# design.net
KiCad netlist of a schematic drawn in Altium Designer
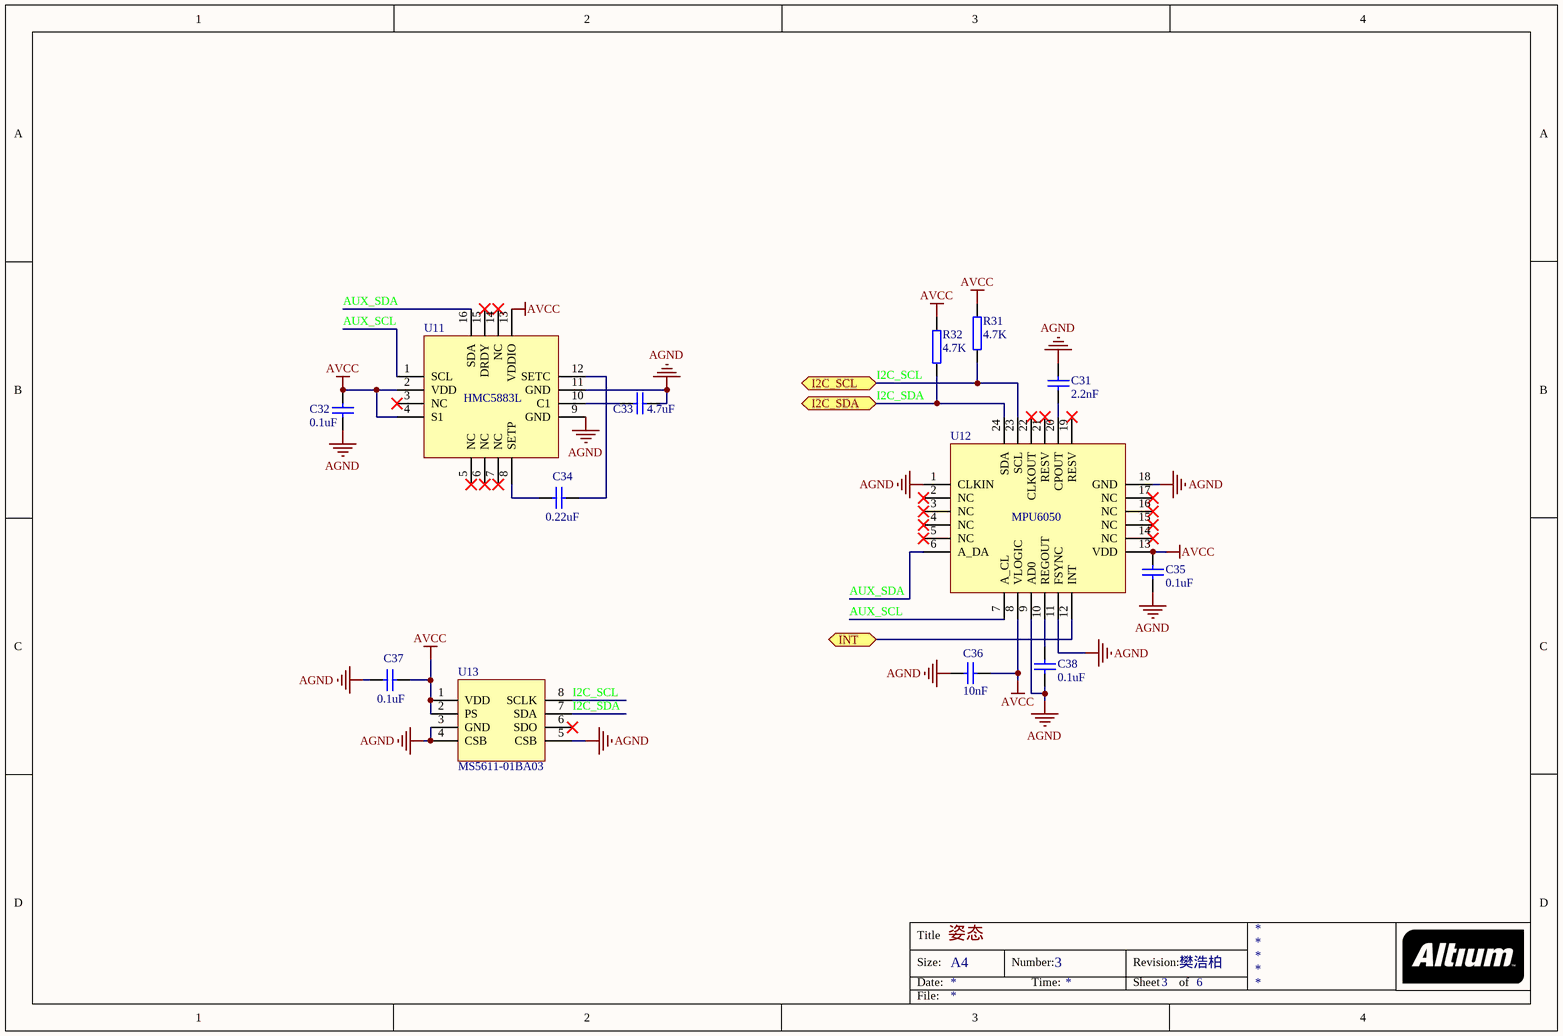
[diagram p0: 姿态.SchDoc]

(export (version "E")
  (design (tool "Eeschema 10.0.6"))
  (components
    (comp (ref "C31") (value "2.2nF") (footprint "CAP-0402") (libsource (lib "Connectors") (part "Cap")))
    (comp (ref "C32") (value "0.1uF") (footprint "CAP-0402") (libsource (lib "Connectors") (part "Cap")))
    (comp (ref "C33") (value "4.7uF") (footprint "CAP-0402") (libsource (lib "Connectors") (part "Cap")))
    (comp (ref "C34") (value "0.22uF") (footprint "CAP-0402") (libsource (lib "Connectors") (part "Cap")))
    (comp (ref "C35") (value "0.1uF") (footprint "CAP-0402") (libsource (lib "Connectors") (part "Cap")))
    (comp (ref "C36") (value "10nF") (footprint "CAP-0402") (libsource (lib "Connectors") (part "Cap")))
    (comp (ref "C37") (value "0.1uF") (footprint "CAP-0402") (libsource (lib "Connectors") (part "Cap")))
    (comp (ref "C38") (value "0.1uF") (footprint "CAP-0402") (libsource (lib "Connectors") (part "Cap")))
    (comp (ref "R31") (value "4.7K") (footprint "RES-0402") (libsource (lib "Connectors") (part "Res")))
    (comp (ref "R32") (value "4.7K") (footprint "RES-0402") (libsource (lib "Connectors") (part "Res")))
    (comp (ref "U11")
      (value "HMC5883L")
      (footprint "QFN-16-3x3MM")
      (libsource (lib "Devices") (part "HMC5883L"))
    )
    (comp (ref "U12")
      (value "MPU6050")
      (footprint "QFN-24-4x4mm")
      (libsource (lib "Devices") (part "MPU6050"))
    )
    (comp (ref "U13") (value "MS5611-01BA03") (footprint "LGA-8") (libsource (lib "Devices") (part "MS5611")))
  )
  (nets
    (net (code "1") (name "/AUX_SCL") (class "Default")
      (node (ref "U11") (pin "1") (pinfunction "SCL_1") (pintype "passive"))
      (node (ref "U12") (pin "7") (pinfunction "A_CL_7") (pintype "passive"))
    )
    (net (code "2") (name "/AUX_SDA") (class "Default")
      (node (ref "U11") (pin "16") (pinfunction "SDA_16") (pintype "passive"))
      (node (ref "U12") (pin "6") (pinfunction "A_DA_6") (pintype "passive"))
    )
    (net (code "3") (name "/I2C_SCL") (class "Default")
      (node (ref "R31") (pin "2") (pinfunction "2_2") (pintype "passive"))
      (node (ref "U12") (pin "23") (pinfunction "SCL_23") (pintype "passive"))
      (node (ref "U13") (pin "8") (pinfunction "SCLK_8") (pintype "passive"))
    )
    (net (code "4") (name "/I2C_SDA") (class "Default")
      (node (ref "R32") (pin "2") (pinfunction "2_2") (pintype "passive"))
      (node (ref "U12") (pin "24") (pinfunction "SDA_24") (pintype "passive"))
      (node (ref "U13") (pin "7") (pinfunction "SDA_7") (pintype "passive"))
    )
    (net (code "5") (name "/INT") (class "Default")
      (node (ref "U12") (pin "12") (pinfunction "INT_12") (pintype "passive"))
    )
    (net (code "6") (name "AGND") (class "Default")
      (node (ref "C31") (pin "2") (pinfunction "2_2") (pintype "passive"))
      (node (ref "C32") (pin "1") (pinfunction "1_1") (pintype "passive"))
      (node (ref "C33") (pin "1") (pinfunction "1_1") (pintype "passive"))
      (node (ref "C35") (pin "1") (pinfunction "1_1") (pintype "passive"))
      (node (ref "C36") (pin "1") (pinfunction "1_1") (pintype "passive"))
      (node (ref "C37") (pin "2") (pinfunction "2_2") (pintype "passive"))
      (node (ref "C38") (pin "1") (pinfunction "1_1") (pintype "passive"))
      (node (ref "U11") (pin "11") (pinfunction "GND_11") (pintype "passive"))
      (node (ref "U11") (pin "9") (pinfunction "GND_9") (pintype "passive"))
      (node (ref "U12") (pin "1") (pinfunction "CLKIN_1") (pintype "passive"))
      (node (ref "U12") (pin "11") (pinfunction "FSYNC_11") (pintype "passive"))
      (node (ref "U12") (pin "18") (pinfunction "GND_18") (pintype "passive"))
      (node (ref "U12") (pin "9") (pinfunction "AD0_9") (pintype "passive"))
      (node (ref "U13") (pin "3") (pinfunction "GND_3") (pintype "passive"))
      (node (ref "U13") (pin "4") (pinfunction "CSB_4") (pintype "passive"))
      (node (ref "U13") (pin "5") (pinfunction "CSB_5") (pintype "passive"))
    )
    (net (code "7") (name "AVCC") (class "Default")
      (node (ref "C32") (pin "2") (pinfunction "2_2") (pintype "passive"))
      (node (ref "C35") (pin "2") (pinfunction "2_2") (pintype "passive"))
      (node (ref "C36") (pin "2") (pinfunction "2_2") (pintype "passive"))
      (node (ref "C37") (pin "1") (pinfunction "1_1") (pintype "passive"))
      (node (ref "R31") (pin "1") (pinfunction "1_1") (pintype "passive"))
      (node (ref "R32") (pin "1") (pinfunction "1_1") (pintype "passive"))
      (node (ref "U11") (pin "13") (pinfunction "VDDIO_13") (pintype "passive"))
      (node (ref "U11") (pin "2") (pinfunction "VDD_2") (pintype "passive"))
      (node (ref "U11") (pin "4") (pinfunction "S1_4") (pintype "passive"))
      (node (ref "U12") (pin "13") (pinfunction "VDD_13") (pintype "passive"))
      (node (ref "U12") (pin "8") (pinfunction "VLOGIC_8") (pintype "passive"))
      (node (ref "U13") (pin "1") (pinfunction "VDD_1") (pintype "passive"))
      (node (ref "U13") (pin "2") (pinfunction "PS_2") (pintype "passive"))
    )
    (net (code "8") (name "Net-(U11-C1)") (class "Default")
      (node (ref "C33") (pin "2") (pinfunction "2_2") (pintype "passive"))
      (node (ref "U11") (pin "10") (pinfunction "C1_10") (pintype "passive"))
    )
    (net (code "9") (name "Net-(U11-SETC)") (class "Default")
      (node (ref "C34") (pin "1") (pinfunction "1_1") (pintype "passive"))
      (node (ref "U11") (pin "12") (pinfunction "SETC_12") (pintype "passive"))
    )
    (net (code "10") (name "Net-(U11-SETP)") (class "Default")
      (node (ref "C34") (pin "2") (pinfunction "2_2") (pintype "passive"))
      (node (ref "U11") (pin "8") (pinfunction "SETP_8") (pintype "passive"))
    )
    (net (code "11") (name "Net-(U12-CPOUT)") (class "Default")
      (node (ref "C31") (pin "1") (pinfunction "1_1") (pintype "passive"))
      (node (ref "U12") (pin "20") (pinfunction "CPOUT_20") (pintype "passive"))
    )
    (net (code "12") (name "Net-(U12-REGOUT)") (class "Default")
      (node (ref "C38") (pin "2") (pinfunction "2_2") (pintype "passive"))
      (node (ref "U12") (pin "10") (pinfunction "REGOUT_10") (pintype "passive"))
    )
    (net (code "13") (name "unconnected-(U11-DRDY-Pad15)") (class "Default")
      (node (ref "U11") (pin "15") (pinfunction "DRDY_15") (pintype "passive+no_connect"))
    )
    (net (code "14") (name "unconnected-(U11-NC-Pad3)") (class "Default")
      (node (ref "U11") (pin "3") (pinfunction "NC_3") (pintype "passive+no_connect"))
    )
    (net (code "15") (name "unconnected-(U11-NC-Pad5)") (class "Default")
      (node (ref "U11") (pin "5") (pinfunction "NC_5") (pintype "passive+no_connect"))
    )
    (net (code "16") (name "unconnected-(U11-NC-Pad6)") (class "Default")
      (node (ref "U11") (pin "6") (pinfunction "NC_6") (pintype "passive+no_connect"))
    )
    (net (code "17") (name "unconnected-(U11-NC-Pad7)") (class "Default")
      (node (ref "U11") (pin "7") (pinfunction "NC_7") (pintype "passive+no_connect"))
    )
    (net (code "18") (name "unconnected-(U11-NC-Pad14)") (class "Default")
      (node (ref "U11") (pin "14") (pinfunction "NC_14") (pintype "passive+no_connect"))
    )
    (net (code "19") (name "unconnected-(U12-CLKOUT-Pad22)") (class "Default")
      (node (ref "U12") (pin "22") (pinfunction "CLKOUT_22") (pintype "passive+no_connect"))
    )
    (net (code "20") (name "unconnected-(U12-NC-Pad2)") (class "Default")
      (node (ref "U12") (pin "2") (pinfunction "NC_2") (pintype "passive+no_connect"))
    )
    (net (code "21") (name "unconnected-(U12-NC-Pad3)") (class "Default")
      (node (ref "U12") (pin "3") (pinfunction "NC_3") (pintype "passive+no_connect"))
    )
    (net (code "22") (name "unconnected-(U12-NC-Pad4)") (class "Default")
      (node (ref "U12") (pin "4") (pinfunction "NC_4") (pintype "passive+no_connect"))
    )
    (net (code "23") (name "unconnected-(U12-NC-Pad5)") (class "Default")
      (node (ref "U12") (pin "5") (pinfunction "NC_5") (pintype "passive+no_connect"))
    )
    (net (code "24") (name "unconnected-(U12-NC-Pad14)") (class "Default")
      (node (ref "U12") (pin "14") (pinfunction "NC_14") (pintype "passive+no_connect"))
    )
    (net (code "25") (name "unconnected-(U12-NC-Pad15)") (class "Default")
      (node (ref "U12") (pin "15") (pinfunction "NC_15") (pintype "passive+no_connect"))
    )
    (net (code "26") (name "unconnected-(U12-NC-Pad16)") (class "Default")
      (node (ref "U12") (pin "16") (pinfunction "NC_16") (pintype "passive+no_connect"))
    )
    (net (code "27") (name "unconnected-(U12-NC-Pad17)") (class "Default")
      (node (ref "U12") (pin "17") (pinfunction "NC_17") (pintype "passive+no_connect"))
    )
    (net (code "28") (name "unconnected-(U12-RESV-Pad19)") (class "Default")
      (node (ref "U12") (pin "19") (pinfunction "RESV_19") (pintype "passive+no_connect"))
    )
    (net (code "29") (name "unconnected-(U12-RESV-Pad21)") (class "Default")
      (node (ref "U12") (pin "21") (pinfunction "RESV_21") (pintype "passive+no_connect"))
    )
    (net (code "30") (name "unconnected-(U13-SDO-Pad6)") (class "Default")
      (node (ref "U13") (pin "6") (pinfunction "SDO_6") (pintype "passive+no_connect"))
    )
  )
)
